# GW-RS485-V41-001.net
KiCad netlist of a schematic drawn in EAGLE
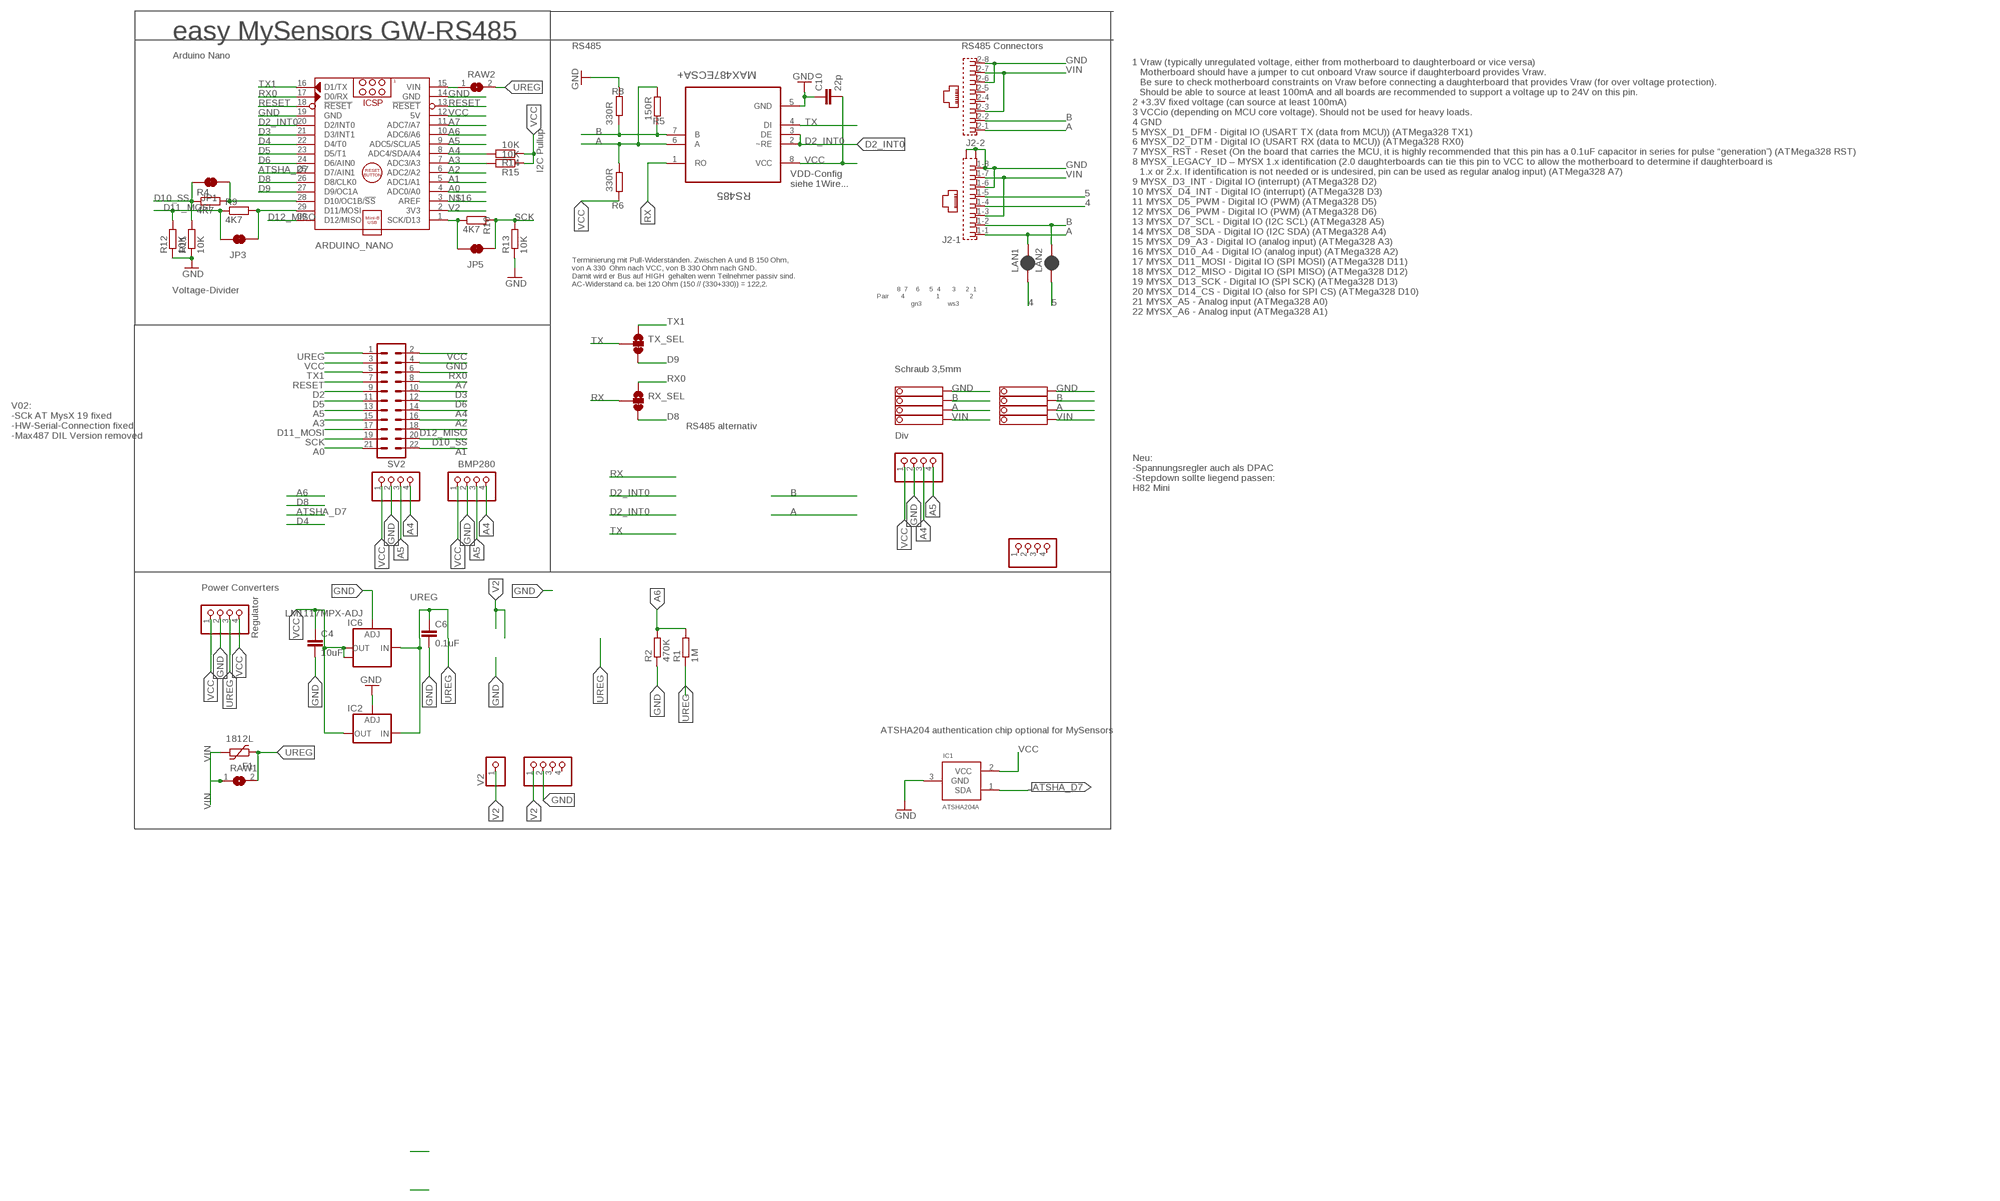
[diagram p0: schematic, sheet 1]

(export (version "E")
  (design (tool "Eeschema 10.0.6"))
  (components
    (comp (ref "ARDUINO_NANO")
      (value "ARDUINO_NANO_OHNE-BOHR")
      (footprint "eagle-import:ARDUINO_NANO")
      (libsource (lib "eagle-import") (part "ARDUINO_NANO_OHNE-BOHR"))
    )
    (comp (ref "BH1750")
      (value "PINHD-1X04_2.54-S")
      (footprint "eagle-import:1X04-S")
      (libsource (lib "eagle-import") (part "PINHD-1X04_2.54-S"))
    )
    (comp (ref "C4")
      (value "10uF")
      (footprint "eagle-import:C1210")
      (libsource (lib "eagle-import") (part "C-EUC1210"))
    )
    (comp (ref "C6")
      (value "0.1uF")
      (footprint "eagle-import:C1206")
      (libsource (lib "eagle-import") (part "C-EUC1206"))
    )
    (comp (ref "C10")
      (value "22p")
      (footprint "eagle-import:C0805")
      (libsource (lib "eagle-import") (part "C-EUC0805"))
    )
    (comp (ref "F1")
      (value "1812L")
      (footprint "eagle-import:1812L")
      (libsource (lib "eagle-import") (part "1812L"))
    )
    (comp (ref "I2C-1")
      (value "PINHD-1X04_2.54-S")
      (footprint "eagle-import:1X04-S")
      (libsource (lib "eagle-import") (part "PINHD-1X04_2.54-S"))
    )
    (comp (ref "I2C-2")
      (value "PINHD-1X04_2.54-S")
      (footprint "eagle-import:1X04-S")
      (libsource (lib "eagle-import") (part "PINHD-1X04_2.54-S"))
    )
    (comp (ref "IC1")
      (value "ATSHA204A")
      (footprint "eagle-import:SOT23")
      (libsource (lib "eagle-import") (part "ATSHA204A"))
    )
    (comp (ref "IC2")
      (value "LD117ADT50TR")
      (footprint "eagle-import:DPACK")
      (libsource (lib "eagle-import") (part "LD117A?DT50TR"))
    )
    (comp (ref "IC6")
      (value "LM1117MPX-ADJ")
      (footprint "eagle-import:SOT223")
      (libsource (lib "eagle-import") (part "LM1117MPX-ADJ"))
    )
    (comp (ref "J2")
      (value "RJ45_2X_NARROW_SHILDPINS_NOCASE")
      (footprint "eagle-import:RJ45_2X_NARROW_SHILDPINS_NOCASE")
      (libsource (lib "eagle-import") (part "RJ45_2X_NARROW_SHILDPINS_NOCASE"))
    )
    (comp (ref "JP1")
      (value "JUMPER-SMT_2_NC_TRACE_SILK")
      (footprint "eagle-import:SMT-JUMPER_2_NC_TRACE_SILK")
      (libsource (lib "eagle-import") (part "JUMPER-SMT_2_NC_TRACE_SILK"))
    )
    (comp (ref "JP2")
      (value "PINHD-1X04_2.54-S")
      (footprint "eagle-import:1X04-S")
      (libsource (lib "eagle-import") (part "PINHD-1X04_2.54-S"))
    )
    (comp (ref "JP3")
      (value "JUMPER-SMT_2_NC_TRACE_SILK")
      (footprint "eagle-import:SMT-JUMPER_2_NC_TRACE_SILK")
      (libsource (lib "eagle-import") (part "JUMPER-SMT_2_NC_TRACE_SILK"))
    )
    (comp (ref "JP5")
      (value "JUMPER-SMT_2_NC_TRACE_SILK")
      (footprint "eagle-import:SMT-JUMPER_2_NC_TRACE_SILK")
      (libsource (lib "eagle-import") (part "JUMPER-SMT_2_NC_TRACE_SILK"))
    )
    (comp (ref "LAN1")
      (value "JUMPER-SMT_2_NC_PASTE_SILK")
      (footprint "eagle-import:SMT-JUMPER_2_NC_PASTE_SILK")
      (libsource (lib "eagle-import") (part "JUMPER-SMT_2_NC_PASTE_SILK"))
    )
    (comp (ref "LAN2")
      (value "JUMPER-SMT_2_NC_PASTE_SILK")
      (footprint "eagle-import:SMT-JUMPER_2_NC_PASTE_SILK")
      (libsource (lib "eagle-import") (part "JUMPER-SMT_2_NC_PASTE_SILK"))
    )
    (comp (ref "R1")
      (value "1M")
      (footprint "eagle-import:R0805")
      (libsource (lib "eagle-import") (part "R-EU_R0805"))
    )
    (comp (ref "R2")
      (value "470K")
      (footprint "eagle-import:R0805")
      (libsource (lib "eagle-import") (part "R-EU_R0805"))
    )
    (comp (ref "R4")
      (value "4K7")
      (footprint "eagle-import:M0805")
      (libsource (lib "eagle-import") (part "R-EU_M0805"))
    )
    (comp (ref "R5")
      (value "150R")
      (footprint "eagle-import:R0805")
      (libsource (lib "eagle-import") (part "R-EU_R0805"))
    )
    (comp (ref "R6")
      (value "330R")
      (footprint "eagle-import:R0805")
      (libsource (lib "eagle-import") (part "R-EU_R0805"))
    )
    (comp (ref "R8")
      (value "330R")
      (footprint "eagle-import:R0805")
      (libsource (lib "eagle-import") (part "R-EU_R0805"))
    )
    (comp (ref "R9")
      (value "4K7")
      (footprint "eagle-import:M0805")
      (libsource (lib "eagle-import") (part "R-EU_M0805"))
    )
    (comp (ref "R10")
      (value "4K7")
      (footprint "eagle-import:M0805")
      (libsource (lib "eagle-import") (part "R-EU_M0805"))
    )
    (comp (ref "R11")
      (value "10K")
      (footprint "eagle-import:M0805")
      (libsource (lib "eagle-import") (part "R-EU_M0805"))
    )
    (comp (ref "R12")
      (value "10K")
      (footprint "eagle-import:M0805")
      (libsource (lib "eagle-import") (part "R-EU_M0805"))
    )
    (comp (ref "R13")
      (value "10K")
      (footprint "eagle-import:M0805")
      (libsource (lib "eagle-import") (part "R-EU_M0805"))
    )
    (comp (ref "R14")
      (value "10K")
      (footprint "eagle-import:R0805")
      (libsource (lib "eagle-import") (part "R-EU_R0805"))
    )
    (comp (ref "R15")
      (value "10K")
      (footprint "eagle-import:R0805")
      (libsource (lib "eagle-import") (part "R-EU_R0805"))
    )
    (comp (ref "RAW1")
      (value "SJ")
      (footprint "eagle-import:SJ")
      (libsource (lib "eagle-import") (part "SJ"))
    )
    (comp (ref "RAW2")
      (value "SJ")
      (footprint "eagle-import:SJ")
      (libsource (lib "eagle-import") (part "SJ"))
    )
    (comp (ref "RS485")
      (value "MAX487ECSA+")
      (footprint "eagle-import:SOIC127P600X175-8N")
      (libsource (lib "eagle-import") (part "MAX487ECSA+"))
    )
    (comp (ref "RX_SEL")
      (value "JUMPER-SMT_3_1-NC_TRACE_SILK")
      (footprint "eagle-import:SMT-JUMPER_3_1-NC_TRACE_SILK")
      (libsource (lib "eagle-import") (part "JUMPER-SMT_3_1-NC_TRACE_SILK"))
    )
    (comp (ref "STEPDWN")
      (value "PINHD-1X04_2.54-S")
      (footprint "eagle-import:1X04-S")
      (libsource (lib "eagle-import") (part "PINHD-1X04_2.54-S"))
    )
    (comp (ref "SV2")
      (value "MA11-2")
      (footprint "eagle-import:MA11-2")
      (libsource (lib "eagle-import") (part "MA11-2"))
    )
    (comp (ref "TX_SEL")
      (value "JUMPER-SMT_3_1-NC_TRACE_SILK")
      (footprint "eagle-import:SMT-JUMPER_3_1-NC_TRACE_SILK")
      (libsource (lib "eagle-import") (part "JUMPER-SMT_3_1-NC_TRACE_SILK"))
    )
    (comp (ref "V2")
      (value "PINHD-1X1")
      (footprint "eagle-import:1X01")
      (libsource (lib "eagle-import") (part "PINHD-1X1"))
    )
    (comp (ref "V2-")
      (value "PINHD-1X04_2.54-S")
      (footprint "eagle-import:1X04-S")
      (libsource (lib "eagle-import") (part "PINHD-1X04_2.54-S"))
    )
    (comp (ref "X1")
      (value "1751264")
      (footprint "eagle-import:1751264")
      (libsource (lib "eagle-import") (part "1751264"))
    )
    (comp (ref "X4")
      (value "1751264")
      (footprint "eagle-import:1751264")
      (libsource (lib "eagle-import") (part "1751264"))
    )
  )
  (nets
    (net (code "1") (name "/4") (class "Default")
      (node (ref "J2") (pin "1-4") (pinfunction "4_1-4") (pintype "passive"))
      (node (ref "LAN1") (pin "1") (pinfunction "1_1") (pintype "passive"))
    )
    (net (code "2") (name "/5") (class "Default")
      (node (ref "J2") (pin "1-5") (pinfunction "5_1-5") (pintype "passive"))
      (node (ref "LAN2") (pin "1") (pinfunction "1_1") (pintype "passive"))
    )
    (net (code "3") (name "/A") (class "Default")
      (node (ref "J2") (pin "1-1") (pinfunction "1_1-1") (pintype "passive"))
      (node (ref "J2") (pin "2-1") (pinfunction "1_2-1") (pintype "passive"))
      (node (ref "LAN1") (pin "2") (pinfunction "2_2") (pintype "passive"))
      (node (ref "R5") (pin "1") (pinfunction "1_1") (pintype "passive"))
      (node (ref "R6") (pin "2") (pinfunction "2_2") (pintype "passive"))
      (node (ref "RS485") (pin "6") (pinfunction "A_6") (pintype "bidirectional"))
      (node (ref "X1") (pin "2") (pinfunction "K_2") (pintype "passive"))
      (node (ref "X4") (pin "2") (pinfunction "K_2") (pintype "passive"))
    )
    (net (code "4") (name "/A0") (class "Default")
      (node (ref "ARDUINO_NANO") (pin "4") (pinfunction "ADC0/A0_4") (pintype "bidirectional"))
      (node (ref "SV2") (pin "21") (pinfunction "21_21") (pintype "passive"))
    )
    (net (code "5") (name "/A1") (class "Default")
      (node (ref "ARDUINO_NANO") (pin "5") (pinfunction "ADC1/A1_5") (pintype "bidirectional"))
      (node (ref "SV2") (pin "22") (pinfunction "22_22") (pintype "passive"))
    )
    (net (code "6") (name "/A2") (class "Default")
      (node (ref "ARDUINO_NANO") (pin "6") (pinfunction "ADC2/A2_6") (pintype "bidirectional"))
      (node (ref "SV2") (pin "16") (pinfunction "16_16") (pintype "passive"))
    )
    (net (code "7") (name "/A3") (class "Default")
      (node (ref "ARDUINO_NANO") (pin "7") (pinfunction "ADC3/A3_7") (pintype "bidirectional"))
      (node (ref "R15") (pin "2") (pinfunction "2_2") (pintype "passive"))
      (node (ref "SV2") (pin "15") (pinfunction "15_15") (pintype "passive"))
    )
    (net (code "8") (name "/A7") (class "Default")
      (node (ref "ARDUINO_NANO") (pin "11") (pinfunction "ADC7/A7_11") (pintype "bidirectional"))
      (node (ref "SV2") (pin "8") (pinfunction "8_8") (pintype "passive"))
    )
    (net (code "9") (name "/ATSHA_D7") (class "Default")
      (node (ref "ARDUINO_NANO") (pin "25") (pinfunction "D7/AIN1_25") (pintype "bidirectional"))
      (node (ref "IC1") (pin "1") (pinfunction "SDA_1") (pintype "bidirectional"))
    )
    (net (code "10") (name "/B") (class "Default")
      (node (ref "J2") (pin "1-2") (pinfunction "2_1-2") (pintype "passive"))
      (node (ref "J2") (pin "2-2") (pinfunction "2_2-2") (pintype "passive"))
      (node (ref "LAN2") (pin "2") (pinfunction "2_2") (pintype "passive"))
      (node (ref "R5") (pin "2") (pinfunction "2_2") (pintype "passive"))
      (node (ref "R8") (pin "1") (pinfunction "1_1") (pintype "passive"))
      (node (ref "RS485") (pin "7") (pinfunction "B_7") (pintype "bidirectional"))
      (node (ref "X1") (pin "3") (pinfunction "K_3") (pintype "passive"))
      (node (ref "X4") (pin "3") (pinfunction "K_3") (pintype "passive"))
    )
    (net (code "11") (name "/D2") (class "Default")
      (node (ref "SV2") (pin "9") (pinfunction "9_9") (pintype "passive"))
    )
    (net (code "12") (name "/D3") (class "Default")
      (node (ref "ARDUINO_NANO") (pin "21") (pinfunction "D3/INT1_21") (pintype "bidirectional"))
      (node (ref "SV2") (pin "10") (pinfunction "10_10") (pintype "passive"))
    )
    (net (code "13") (name "/D4") (class "Default")
      (node (ref "ARDUINO_NANO") (pin "22") (pinfunction "D4/T0_22") (pintype "bidirectional"))
    )
    (net (code "14") (name "/D5") (class "Default")
      (node (ref "ARDUINO_NANO") (pin "23") (pinfunction "D5/T1_23") (pintype "bidirectional"))
      (node (ref "SV2") (pin "11") (pinfunction "11_11") (pintype "passive"))
    )
    (net (code "15") (name "/D6") (class "Default")
      (node (ref "ARDUINO_NANO") (pin "24") (pinfunction "D6/AIN0_24") (pintype "bidirectional"))
      (node (ref "SV2") (pin "12") (pinfunction "12_12") (pintype "passive"))
    )
    (net (code "16") (name "/D8") (class "Default")
      (node (ref "ARDUINO_NANO") (pin "26") (pinfunction "D8/CLK0_26") (pintype "bidirectional"))
      (node (ref "RX_SEL") (pin "3") (pinfunction "3_3") (pintype "passive"))
    )
    (net (code "17") (name "/D9") (class "Default")
      (node (ref "ARDUINO_NANO") (pin "27") (pinfunction "D9/OC1A_27") (pintype "bidirectional"))
      (node (ref "TX_SEL") (pin "3") (pinfunction "3_3") (pintype "passive"))
    )
    (net (code "18") (name "/D10_SS") (class "Default")
      (node (ref "JP1") (pin "1") (pinfunction "1_1") (pintype "passive"))
      (node (ref "R11") (pin "2") (pinfunction "2_2") (pintype "passive"))
      (node (ref "R4") (pin "1") (pinfunction "1_1") (pintype "passive"))
      (node (ref "SV2") (pin "20") (pinfunction "20_20") (pintype "passive"))
    )
    (net (code "19") (name "/D11_MOSI") (class "Default")
      (node (ref "JP3") (pin "1") (pinfunction "1_1") (pintype "passive"))
      (node (ref "R12") (pin "2") (pinfunction "2_2") (pintype "passive"))
      (node (ref "R9") (pin "1") (pinfunction "1_1") (pintype "passive"))
      (node (ref "SV2") (pin "17") (pinfunction "17_17") (pintype "passive"))
    )
    (net (code "20") (name "/D12_MISO") (class "Default")
      (node (ref "ARDUINO_NANO") (pin "30") (pinfunction "D12/MISO_30") (pintype "bidirectional"))
      (node (ref "SV2") (pin "18") (pinfunction "18_18") (pintype "passive"))
    )
    (net (code "21") (name "/N$16") (class "Default")
      (node (ref "ARDUINO_NANO") (pin "3") (pinfunction "AREF_3") (pintype "input"))
    )
    (net (code "22") (name "/RESET") (class "Default")
      (node (ref "ARDUINO_NANO") (pin "13") (pinfunction "~{RESET}_13") (pintype "input"))
      (node (ref "ARDUINO_NANO") (pin "18") (pinfunction "~{RESET}_18") (pintype "input"))
      (node (ref "SV2") (pin "7") (pinfunction "7_7") (pintype "passive"))
    )
    (net (code "23") (name "/RX0") (class "Default")
      (node (ref "ARDUINO_NANO") (pin "17") (pinfunction "D0/RX_17") (pintype "bidirectional"))
      (node (ref "RX_SEL") (pin "1") (pinfunction "1_1") (pintype "passive"))
      (node (ref "SV2") (pin "6") (pinfunction "6_6") (pintype "passive"))
    )
    (net (code "24") (name "/SCK") (class "Default")
      (node (ref "JP5") (pin "2") (pinfunction "2_2") (pintype "passive"))
      (node (ref "R10") (pin "2") (pinfunction "2_2") (pintype "passive"))
      (node (ref "R13") (pin "2") (pinfunction "2_2") (pintype "passive"))
      (node (ref "SV2") (pin "19") (pinfunction "19_19") (pintype "passive"))
    )
    (net (code "25") (name "/TX") (class "Default")
      (node (ref "RS485") (pin "4") (pinfunction "DI_4") (pintype "input"))
      (node (ref "TX_SEL") (pin "2") (pinfunction "2_2") (pintype "passive"))
    )
    (net (code "26") (name "/TX1") (class "Default")
      (node (ref "ARDUINO_NANO") (pin "16") (pinfunction "D1/TX_16") (pintype "bidirectional"))
      (node (ref "SV2") (pin "5") (pinfunction "5_5") (pintype "passive"))
      (node (ref "TX_SEL") (pin "1") (pinfunction "1_1") (pintype "passive"))
    )
    (net (code "27") (name "/VIN") (class "Default")
      (node (ref "F1") (pin "P$2") (pinfunction "2_P$2") (pintype "passive"))
      (node (ref "J2") (pin "1-3") (pinfunction "3_1-3") (pintype "passive"))
      (node (ref "J2") (pin "1-7") (pinfunction "7_1-7") (pintype "passive"))
      (node (ref "J2") (pin "2-3") (pinfunction "3_2-3") (pintype "passive"))
      (node (ref "J2") (pin "2-7") (pinfunction "7_2-7") (pintype "passive"))
      (node (ref "RAW1") (pin "1") (pinfunction "1_1") (pintype "passive"))
      (node (ref "X1") (pin "1") (pinfunction "K_1") (pintype "passive"))
      (node (ref "X4") (pin "1") (pinfunction "K_1") (pintype "passive"))
    )
    (net (code "28") (name "A4") (class "Default")
      (node (ref "ARDUINO_NANO") (pin "8") (pinfunction "ADC4/SDA/A4_8") (pintype "bidirectional"))
      (node (ref "BH1750") (pin "4") (pinfunction "4_4") (pintype "passive"))
      (node (ref "I2C-1") (pin "4") (pinfunction "4_4") (pintype "passive"))
      (node (ref "I2C-2") (pin "3") (pinfunction "3_3") (pintype "passive"))
      (node (ref "R14") (pin "2") (pinfunction "2_2") (pintype "passive"))
      (node (ref "SV2") (pin "14") (pinfunction "14_14") (pintype "passive"))
    )
    (net (code "29") (name "A5") (class "Default")
      (node (ref "ARDUINO_NANO") (pin "9") (pinfunction "ADC5/SCL/A5_9") (pintype "bidirectional"))
      (node (ref "BH1750") (pin "3") (pinfunction "3_3") (pintype "passive"))
      (node (ref "I2C-1") (pin "3") (pinfunction "3_3") (pintype "passive"))
      (node (ref "I2C-2") (pin "4") (pinfunction "4_4") (pintype "passive"))
      (node (ref "SV2") (pin "13") (pinfunction "13_13") (pintype "passive"))
    )
    (net (code "30") (name "A6") (class "Default")
      (node (ref "ARDUINO_NANO") (pin "10") (pinfunction "ADC6/A6_10") (pintype "bidirectional"))
      (node (ref "R1") (pin "2") (pinfunction "2_2") (pintype "passive"))
      (node (ref "R2") (pin "2") (pinfunction "2_2") (pintype "passive"))
    )
    (net (code "31") (name "D2_INT0") (class "Default")
      (node (ref "ARDUINO_NANO") (pin "20") (pinfunction "D2/INT0_20") (pintype "bidirectional"))
      (node (ref "RS485") (pin "2") (pinfunction "~{RE}_2") (pintype "input"))
      (node (ref "RS485") (pin "3") (pinfunction "DE_3") (pintype "input"))
    )
    (net (code "32") (name "GND") (class "Default")
      (node (ref "ARDUINO_NANO") (pin "14") (pinfunction "GND_14") (pintype "power_in"))
      (node (ref "ARDUINO_NANO") (pin "19") (pinfunction "GND_19") (pintype "power_in"))
      (node (ref "BH1750") (pin "2") (pinfunction "2_2") (pintype "passive"))
      (node (ref "C10") (pin "1") (pinfunction "1_1") (pintype "passive"))
      (node (ref "C4") (pin "2") (pinfunction "2_2") (pintype "passive"))
      (node (ref "C6") (pin "2") (pinfunction "2_2") (pintype "passive"))
      (node (ref "I2C-1") (pin "2") (pinfunction "2_2") (pintype "passive"))
      (node (ref "I2C-2") (pin "2") (pinfunction "2_2") (pintype "passive"))
      (node (ref "IC1") (pin "3") (pinfunction "GND_3") (pintype "bidirectional"))
      (node (ref "IC2") (pin "1") (pinfunction "ADJ_1") (pintype "input"))
      (node (ref "IC6") (pin "1") (pinfunction "ADJ_1") (pintype "input"))
      (node (ref "J2") (pin "1-6") (pinfunction "6_1-6") (pintype "passive"))
      (node (ref "J2") (pin "1-8") (pinfunction "8_1-8") (pintype "passive"))
      (node (ref "J2") (pin "2-6") (pinfunction "6_2-6") (pintype "passive"))
      (node (ref "J2") (pin "2-8") (pinfunction "8_2-8") (pintype "passive"))
      (node (ref "J2") (pin "G1") (pinfunction "S1_G1") (pintype "passive"))
      (node (ref "J2") (pin "G3") (pinfunction "S2_G3") (pintype "passive"))
      (node (ref "R11") (pin "1") (pinfunction "1_1") (pintype "passive"))
      (node (ref "R12") (pin "1") (pinfunction "1_1") (pintype "passive"))
      (node (ref "R13") (pin "1") (pinfunction "1_1") (pintype "passive"))
      (node (ref "R2") (pin "1") (pinfunction "1_1") (pintype "passive"))
      (node (ref "R8") (pin "2") (pinfunction "2_2") (pintype "passive"))
      (node (ref "RS485") (pin "5") (pinfunction "GND_5") (pintype "passive"))
      (node (ref "STEPDWN") (pin "2") (pinfunction "2_2") (pintype "passive"))
      (node (ref "SV2") (pin "4") (pinfunction "4_4") (pintype "passive"))
      (node (ref "V2-") (pin "2") (pinfunction "2_2") (pintype "passive"))
      (node (ref "X1") (pin "4") (pinfunction "K_4") (pintype "passive"))
      (node (ref "X4") (pin "4") (pinfunction "K_4") (pintype "passive"))
    )
    (net (code "33") (name "Net-(ARDUINO_NANO-D10{slash}OC1B{slash}~{SS})") (class "Default")
      (node (ref "ARDUINO_NANO") (pin "28") (pinfunction "D10/OC1B/~{SS}_28") (pintype "bidirectional"))
      (node (ref "JP1") (pin "2") (pinfunction "2_2") (pintype "passive"))
      (node (ref "R4") (pin "2") (pinfunction "2_2") (pintype "passive"))
    )
    (net (code "34") (name "Net-(ARDUINO_NANO-D11{slash}MOSI)") (class "Default")
      (node (ref "ARDUINO_NANO") (pin "29") (pinfunction "D11/MOSI_29") (pintype "bidirectional"))
      (node (ref "JP3") (pin "2") (pinfunction "2_2") (pintype "passive"))
      (node (ref "R9") (pin "2") (pinfunction "2_2") (pintype "passive"))
    )
    (net (code "35") (name "Net-(ARDUINO_NANO-SCK{slash}D13)") (class "Default")
      (node (ref "ARDUINO_NANO") (pin "1") (pinfunction "SCK/D13_1") (pintype "bidirectional"))
      (node (ref "JP5") (pin "1") (pinfunction "1_1") (pintype "passive"))
      (node (ref "R10") (pin "1") (pinfunction "1_1") (pintype "passive"))
    )
    (net (code "36") (name "Net-(ARDUINO_NANO-VIN)") (class "Default")
      (node (ref "ARDUINO_NANO") (pin "15") (pinfunction "VIN_15") (pintype "power_in"))
      (node (ref "RAW2") (pin "1") (pinfunction "1_1") (pintype "passive"))
    )
    (net (code "37") (name "RX") (class "Default")
      (node (ref "RS485") (pin "1") (pinfunction "RO_1") (pintype "output"))
      (node (ref "RX_SEL") (pin "2") (pinfunction "2_2") (pintype "passive"))
    )
    (net (code "38") (name "UREG") (class "Default")
      (node (ref "C6") (pin "1") (pinfunction "1_1") (pintype "passive"))
      (node (ref "F1") (pin "P$1") (pinfunction "1_P$1") (pintype "passive"))
      (node (ref "IC2") (pin "3") (pinfunction "IN_3") (pintype "input"))
      (node (ref "IC6") (pin "3") (pinfunction "IN_3") (pintype "input"))
      (node (ref "R1") (pin "1") (pinfunction "1_1") (pintype "passive"))
      (node (ref "RAW1") (pin "2") (pinfunction "2_2") (pintype "passive"))
      (node (ref "RAW2") (pin "2") (pinfunction "2_2") (pintype "passive"))
      (node (ref "STEPDWN") (pin "3") (pinfunction "3_3") (pintype "passive"))
      (node (ref "SV2") (pin "1") (pinfunction "1_1") (pintype "passive"))
    )
    (net (code "39") (name "V2") (class "Default")
      (node (ref "ARDUINO_NANO") (pin "2") (pinfunction "3V3_2") (pintype "output"))
      (node (ref "V2") (pin "1") (pinfunction "1_1") (pintype "passive"))
      (node (ref "V2-") (pin "1") (pinfunction "1_1") (pintype "passive"))
    )
    (net (code "40") (name "VCC") (class "Default")
      (node (ref "ARDUINO_NANO") (pin "12") (pinfunction "5V_12") (pintype "power_in"))
      (node (ref "BH1750") (pin "1") (pinfunction "1_1") (pintype "passive"))
      (node (ref "C10") (pin "2") (pinfunction "2_2") (pintype "passive"))
      (node (ref "C4") (pin "1") (pinfunction "1_1") (pintype "passive"))
      (node (ref "I2C-1") (pin "1") (pinfunction "1_1") (pintype "passive"))
      (node (ref "I2C-2") (pin "1") (pinfunction "1_1") (pintype "passive"))
      (node (ref "IC1") (pin "2") (pinfunction "VCC_2") (pintype "bidirectional"))
      (node (ref "IC2") (pin "4") (pinfunction "OUT_4") (pintype "passive"))
      (node (ref "IC6") (pin "2") (pinfunction "OUT_2") (pintype "passive"))
      (node (ref "IC6") (pin "TAB") (pinfunction "OUT1_TAB") (pintype "passive"))
      (node (ref "R14") (pin "1") (pinfunction "1_1") (pintype "passive"))
      (node (ref "R15") (pin "1") (pinfunction "1_1") (pintype "passive"))
      (node (ref "R6") (pin "1") (pinfunction "1_1") (pintype "passive"))
      (node (ref "RS485") (pin "8") (pinfunction "VCC_8") (pintype "power_in"))
      (node (ref "STEPDWN") (pin "1") (pinfunction "1_1") (pintype "passive"))
      (node (ref "STEPDWN") (pin "4") (pinfunction "4_4") (pintype "passive"))
      (node (ref "SV2") (pin "2") (pinfunction "2_2") (pintype "passive"))
      (node (ref "SV2") (pin "3") (pinfunction "3_3") (pintype "passive"))
    )
    (net (code "41") (name "unconnected-(J2B-4-Pad2-4)") (class "Default")
      (node (ref "J2") (pin "2-4") (pinfunction "4_2-4") (pintype "passive"))
    )
    (net (code "42") (name "unconnected-(J2B-5-Pad2-5)") (class "Default")
      (node (ref "J2") (pin "2-5") (pinfunction "5_2-5") (pintype "passive"))
    )
    (net (code "43") (name "unconnected-(JP2-Pad1)") (class "Default")
      (node (ref "JP2") (pin "1") (pinfunction "1_1") (pintype "passive"))
    )
    (net (code "44") (name "unconnected-(JP2-Pad2)") (class "Default")
      (node (ref "JP2") (pin "2") (pinfunction "2_2") (pintype "passive"))
    )
    (net (code "45") (name "unconnected-(JP2-Pad3)") (class "Default")
      (node (ref "JP2") (pin "3") (pinfunction "3_3") (pintype "passive"))
    )
    (net (code "46") (name "unconnected-(JP2-Pad4)") (class "Default")
      (node (ref "JP2") (pin "4") (pinfunction "4_4") (pintype "passive"))
    )
    (net (code "47") (name "unconnected-(V2--Pad3)") (class "Default")
      (node (ref "V2-") (pin "3") (pinfunction "3_3") (pintype "passive"))
    )
    (net (code "48") (name "unconnected-(V2--Pad4)") (class "Default")
      (node (ref "V2-") (pin "4") (pinfunction "4_4") (pintype "passive"))
    )
  )
)
